# Connectors2.net
KiCad netlist of a schematic drawn in Altium Designer
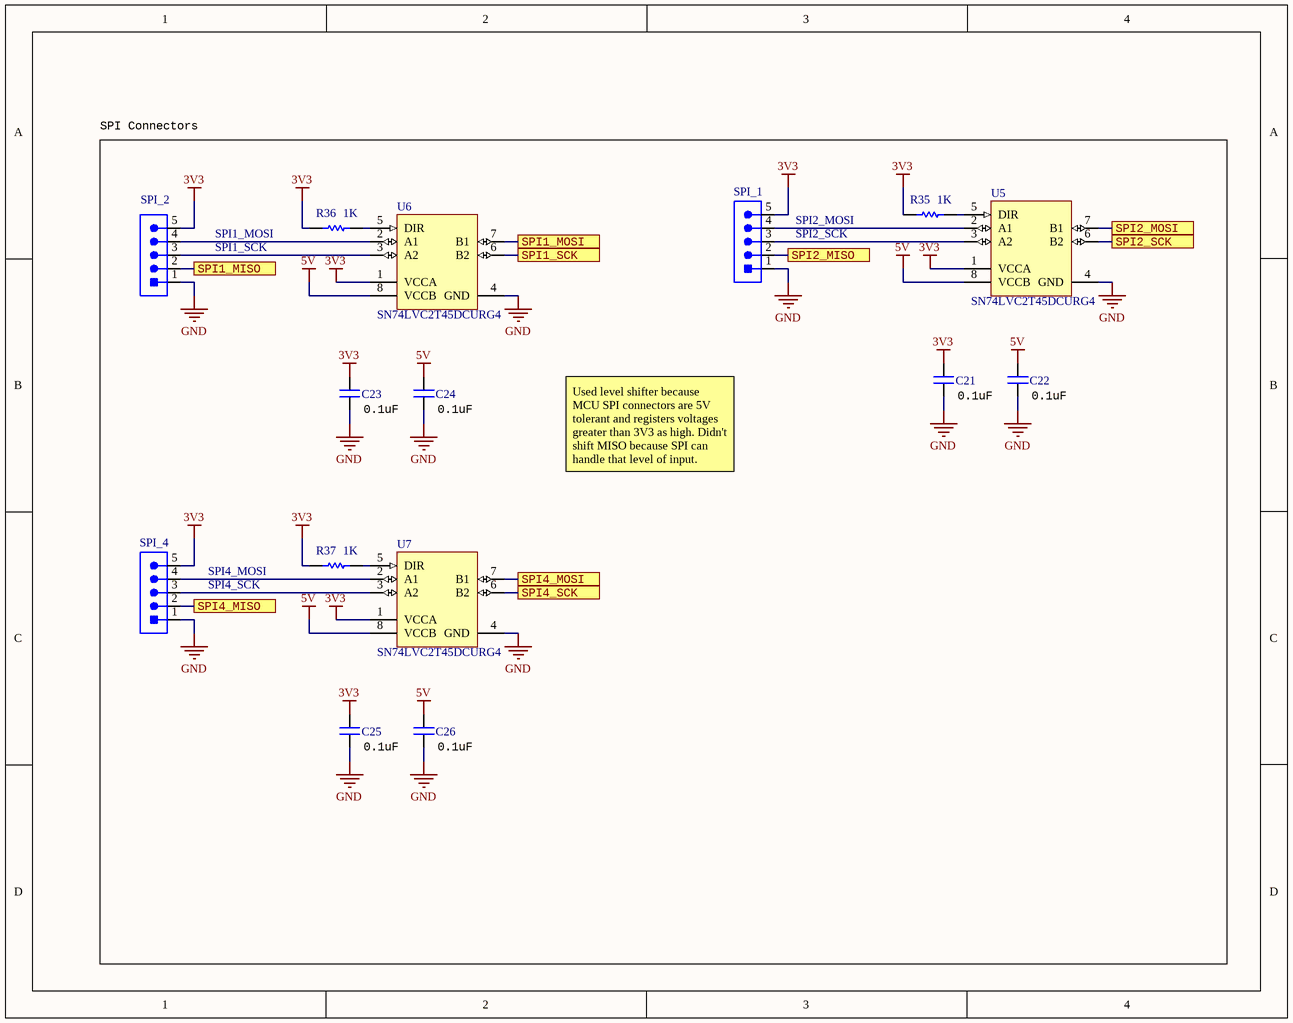
[diagram p0: Connectors2.SchDoc]

(export (version "E")
  (design (tool "Eeschema 10.0.6"))
  (components
    (comp (ref "C21")
      (value "0.1uF")
      (footprint "CAPC0603(1608)55_N")
      (description "CAP CER 0.1UF 16V X7R 0603")
      (fields (field (name "MPN") "CC0603KRX7R7BB104") (field (name "MANUFACTURER") "Yageo"))
      (libsource (lib "UWRT_Schematic_Library_2020") (part "CAP_0.1uF_16V_0603"))
    )
    (comp (ref "C22")
      (value "0.1uF")
      (footprint "CAPC0603(1608)55_N")
      (description "CAP CER 0.1UF 16V X7R 0603")
      (fields (field (name "MPN") "CC0603KRX7R7BB104") (field (name "MANUFACTURER") "Yageo"))
      (libsource (lib "UWRT_Schematic_Library_2020") (part "CAP_0.1uF_16V_0603"))
    )
    (comp (ref "C23")
      (value "0.1uF")
      (footprint "CAPC0603(1608)55_N")
      (description "CAP CER 0.1UF 16V X7R 0603")
      (fields (field (name "MPN") "CC0603KRX7R7BB104") (field (name "MANUFACTURER") "Yageo"))
      (libsource (lib "UWRT_Schematic_Library_2020") (part "CAP_0.1uF_16V_0603"))
    )
    (comp (ref "C24")
      (value "0.1uF")
      (footprint "CAPC0603(1608)55_N")
      (description "CAP CER 0.1UF 16V X7R 0603")
      (fields (field (name "MPN") "CC0603KRX7R7BB104") (field (name "MANUFACTURER") "Yageo"))
      (libsource (lib "UWRT_Schematic_Library_2020") (part "CAP_0.1uF_16V_0603"))
    )
    (comp (ref "C25")
      (value "0.1uF")
      (footprint "CAPC0603(1608)55_N")
      (description "CAP CER 0.1UF 16V X7R 0603")
      (fields (field (name "MPN") "CC0603KRX7R7BB104") (field (name "MANUFACTURER") "Yageo"))
      (libsource (lib "UWRT_Schematic_Library_2020") (part "CAP_0.1uF_16V_0603"))
    )
    (comp (ref "C26")
      (value "0.1uF")
      (footprint "CAPC0603(1608)55_N")
      (description "CAP CER 0.1UF 16V X7R 0603")
      (fields (field (name "MPN") "CC0603KRX7R7BB104") (field (name "MANUFACTURER") "Yageo"))
      (libsource (lib "UWRT_Schematic_Library_2020") (part "CAP_0.1uF_16V_0603"))
    )
    (comp (ref "R35")
      (value "1K")
      (footprint "RESC0603(1608)_N")
      (description "RES SMD 1K OHM 5% 1/10W 0603")
      (fields (field (name "TOLERANCE") "5%") (field (name "MANUFACTURER") "Yageo"))
      (libsource (lib "UWRT_Schematic_Library_2020") (part "RES_1K_0603"))
    )
    (comp (ref "R36")
      (value "1K")
      (footprint "RESC0603(1608)_N")
      (description "RES SMD 1K OHM 5% 1/10W 0603")
      (fields (field (name "TOLERANCE") "5%") (field (name "MANUFACTURER") "Yageo"))
      (libsource (lib "UWRT_Schematic_Library_2020") (part "RES_1K_0603"))
    )
    (comp (ref "R37")
      (value "1K")
      (footprint "RESC0603(1608)_N")
      (description "RES SMD 1K OHM 5% 1/10W 0603")
      (fields (field (name "TOLERANCE") "5%") (field (name "MANUFACTURER") "Yageo"))
      (libsource (lib "UWRT_Schematic_Library_2020") (part "RES_1K_0603"))
    )
    (comp (ref "SPI_1")
      (value "CON_5M")
      (footprint "JST-B5B-SM4-TB")
      (libsource (lib "UWRT_Schematic_Library_2020") (part "CON_5M"))
    )
    (comp (ref "SPI_2")
      (value "CON_5M")
      (footprint "JST-B5B-SM4-TB")
      (libsource (lib "UWRT_Schematic_Library_2020") (part "CON_5M"))
    )
    (comp (ref "SPI_4")
      (value "CON_5M")
      (footprint "JST-B5B-SM4-TB")
      (libsource (lib "UWRT_Schematic_Library_2020") (part "CON_5M"))
    )
    (comp (ref "U5")
      (value "SN74LVC2T45DCURG4")
      (footprint "DCU0008A_L")
      (fields
        (field (name "MANUFACTURER") "Texas Instruments")
        (field (name "GENERIC PART NUMBER") "SN74LVC2T45")
      )
      (libsource (lib "Altium Content Vault") (part "TI-SN74XVC2T45-8"))
    )
    (comp (ref "U6")
      (value "SN74LVC2T45DCURG4")
      (footprint "DCU0008A_L")
      (fields
        (field (name "MANUFACTURER") "Texas Instruments")
        (field (name "GENERIC PART NUMBER") "SN74LVC2T45")
      )
      (libsource (lib "Altium Content Vault") (part "TI-SN74XVC2T45-8"))
    )
    (comp (ref "U7")
      (value "SN74LVC2T45DCURG4")
      (footprint "DCU0008A_L")
      (fields
        (field (name "MANUFACTURER") "Texas Instruments")
        (field (name "GENERIC PART NUMBER") "SN74LVC2T45")
      )
      (libsource (lib "Altium Content Vault") (part "TI-SN74XVC2T45-8"))
    )
  )
  (nets
    (net (code "1") (name "/SPI1_MISO") (class "Default")
      (node (ref "SPI_2") (pin "2") (pinfunction "2_2") (pintype "passive"))
    )
    (net (code "2") (name "/SPI1_MOSI") (class "Default")
      (node (ref "U6") (pin "7") (pinfunction "B1_7") (pintype "bidirectional"))
    )
    (net (code "3") (name "/SPI1_SCK") (class "Default")
      (node (ref "U6") (pin "6") (pinfunction "B2_6") (pintype "bidirectional"))
    )
    (net (code "4") (name "/SPI2_MISO") (class "Default")
      (node (ref "SPI_1") (pin "2") (pinfunction "2_2") (pintype "passive"))
    )
    (net (code "5") (name "/SPI2_MOSI") (class "Default")
      (node (ref "U5") (pin "7") (pinfunction "B1_7") (pintype "bidirectional"))
    )
    (net (code "6") (name "/SPI2_SCK") (class "Default")
      (node (ref "U5") (pin "6") (pinfunction "B2_6") (pintype "bidirectional"))
    )
    (net (code "7") (name "/SPI4_MISO") (class "Default")
      (node (ref "SPI_4") (pin "2") (pinfunction "2_2") (pintype "passive"))
    )
    (net (code "8") (name "/SPI4_MOSI") (class "Default")
      (node (ref "U7") (pin "7") (pinfunction "B1_7") (pintype "bidirectional"))
    )
    (net (code "9") (name "/SPI4_SCK") (class "Default")
      (node (ref "U7") (pin "6") (pinfunction "B2_6") (pintype "bidirectional"))
    )
    (net (code "10") (name "3V3") (class "Default")
      (node (ref "C21") (pin "2") (pinfunction "2_2") (pintype "passive"))
      (node (ref "C23") (pin "2") (pinfunction "2_2") (pintype "passive"))
      (node (ref "C25") (pin "2") (pinfunction "2_2") (pintype "passive"))
      (node (ref "R35") (pin "1") (pinfunction "1_1") (pintype "passive"))
      (node (ref "R36") (pin "1") (pinfunction "1_1") (pintype "passive"))
      (node (ref "R37") (pin "1") (pinfunction "1_1") (pintype "passive"))
      (node (ref "SPI_1") (pin "5") (pinfunction "5_5") (pintype "passive"))
      (node (ref "SPI_2") (pin "5") (pinfunction "5_5") (pintype "passive"))
      (node (ref "SPI_4") (pin "5") (pinfunction "5_5") (pintype "passive"))
      (node (ref "U5") (pin "1") (pinfunction "VCCA_1") (pintype "power_in"))
      (node (ref "U6") (pin "1") (pinfunction "VCCA_1") (pintype "power_in"))
      (node (ref "U7") (pin "1") (pinfunction "VCCA_1") (pintype "power_in"))
    )
    (net (code "11") (name "5V") (class "Default")
      (node (ref "C22") (pin "2") (pinfunction "2_2") (pintype "passive"))
      (node (ref "C24") (pin "2") (pinfunction "2_2") (pintype "passive"))
      (node (ref "C26") (pin "2") (pinfunction "2_2") (pintype "passive"))
      (node (ref "U5") (pin "8") (pinfunction "VCCB_8") (pintype "power_in"))
      (node (ref "U6") (pin "8") (pinfunction "VCCB_8") (pintype "power_in"))
      (node (ref "U7") (pin "8") (pinfunction "VCCB_8") (pintype "power_in"))
    )
    (net (code "12") (name "GND") (class "Default")
      (node (ref "C21") (pin "1") (pinfunction "1_1") (pintype "passive"))
      (node (ref "C22") (pin "1") (pinfunction "1_1") (pintype "passive"))
      (node (ref "C23") (pin "1") (pinfunction "1_1") (pintype "passive"))
      (node (ref "C24") (pin "1") (pinfunction "1_1") (pintype "passive"))
      (node (ref "C25") (pin "1") (pinfunction "1_1") (pintype "passive"))
      (node (ref "C26") (pin "1") (pinfunction "1_1") (pintype "passive"))
      (node (ref "SPI_1") (pin "1") (pinfunction "1_1") (pintype "passive"))
      (node (ref "SPI_2") (pin "1") (pinfunction "1_1") (pintype "passive"))
      (node (ref "SPI_4") (pin "1") (pinfunction "1_1") (pintype "passive"))
      (node (ref "U5") (pin "4") (pinfunction "GND_4") (pintype "power_in"))
      (node (ref "U6") (pin "4") (pinfunction "GND_4") (pintype "power_in"))
      (node (ref "U7") (pin "4") (pinfunction "GND_4") (pintype "power_in"))
    )
    (net (code "13") (name "Net-(U5-A1)") (class "Default")
      (node (ref "SPI_1") (pin "4") (pinfunction "4_4") (pintype "passive"))
      (node (ref "U5") (pin "2") (pinfunction "A1_2") (pintype "bidirectional"))
    )
    (net (code "14") (name "Net-(U5-A2)") (class "Default")
      (node (ref "SPI_1") (pin "3") (pinfunction "3_3") (pintype "passive"))
      (node (ref "U5") (pin "3") (pinfunction "A2_3") (pintype "bidirectional"))
    )
    (net (code "15") (name "Net-(U5-DIR)") (class "Default")
      (node (ref "R35") (pin "2") (pinfunction "2_2") (pintype "passive"))
      (node (ref "U5") (pin "5") (pinfunction "DIR_5") (pintype "input"))
    )
    (net (code "16") (name "Net-(U6-A1)") (class "Default")
      (node (ref "SPI_2") (pin "4") (pinfunction "4_4") (pintype "passive"))
      (node (ref "U6") (pin "2") (pinfunction "A1_2") (pintype "bidirectional"))
    )
    (net (code "17") (name "Net-(U6-A2)") (class "Default")
      (node (ref "SPI_2") (pin "3") (pinfunction "3_3") (pintype "passive"))
      (node (ref "U6") (pin "3") (pinfunction "A2_3") (pintype "bidirectional"))
    )
    (net (code "18") (name "Net-(U6-DIR)") (class "Default")
      (node (ref "R36") (pin "2") (pinfunction "2_2") (pintype "passive"))
      (node (ref "U6") (pin "5") (pinfunction "DIR_5") (pintype "input"))
    )
    (net (code "19") (name "Net-(U7-A1)") (class "Default")
      (node (ref "SPI_4") (pin "4") (pinfunction "4_4") (pintype "passive"))
      (node (ref "U7") (pin "2") (pinfunction "A1_2") (pintype "bidirectional"))
    )
    (net (code "20") (name "Net-(U7-A2)") (class "Default")
      (node (ref "SPI_4") (pin "3") (pinfunction "3_3") (pintype "passive"))
      (node (ref "U7") (pin "3") (pinfunction "A2_3") (pintype "bidirectional"))
    )
    (net (code "21") (name "Net-(U7-DIR)") (class "Default")
      (node (ref "R37") (pin "2") (pinfunction "2_2") (pintype "passive"))
      (node (ref "U7") (pin "5") (pinfunction "DIR_5") (pintype "input"))
    )
  )
)
